# Instrumentation_Amp.net
KiCad netlist of a schematic drawn in Altium Designer
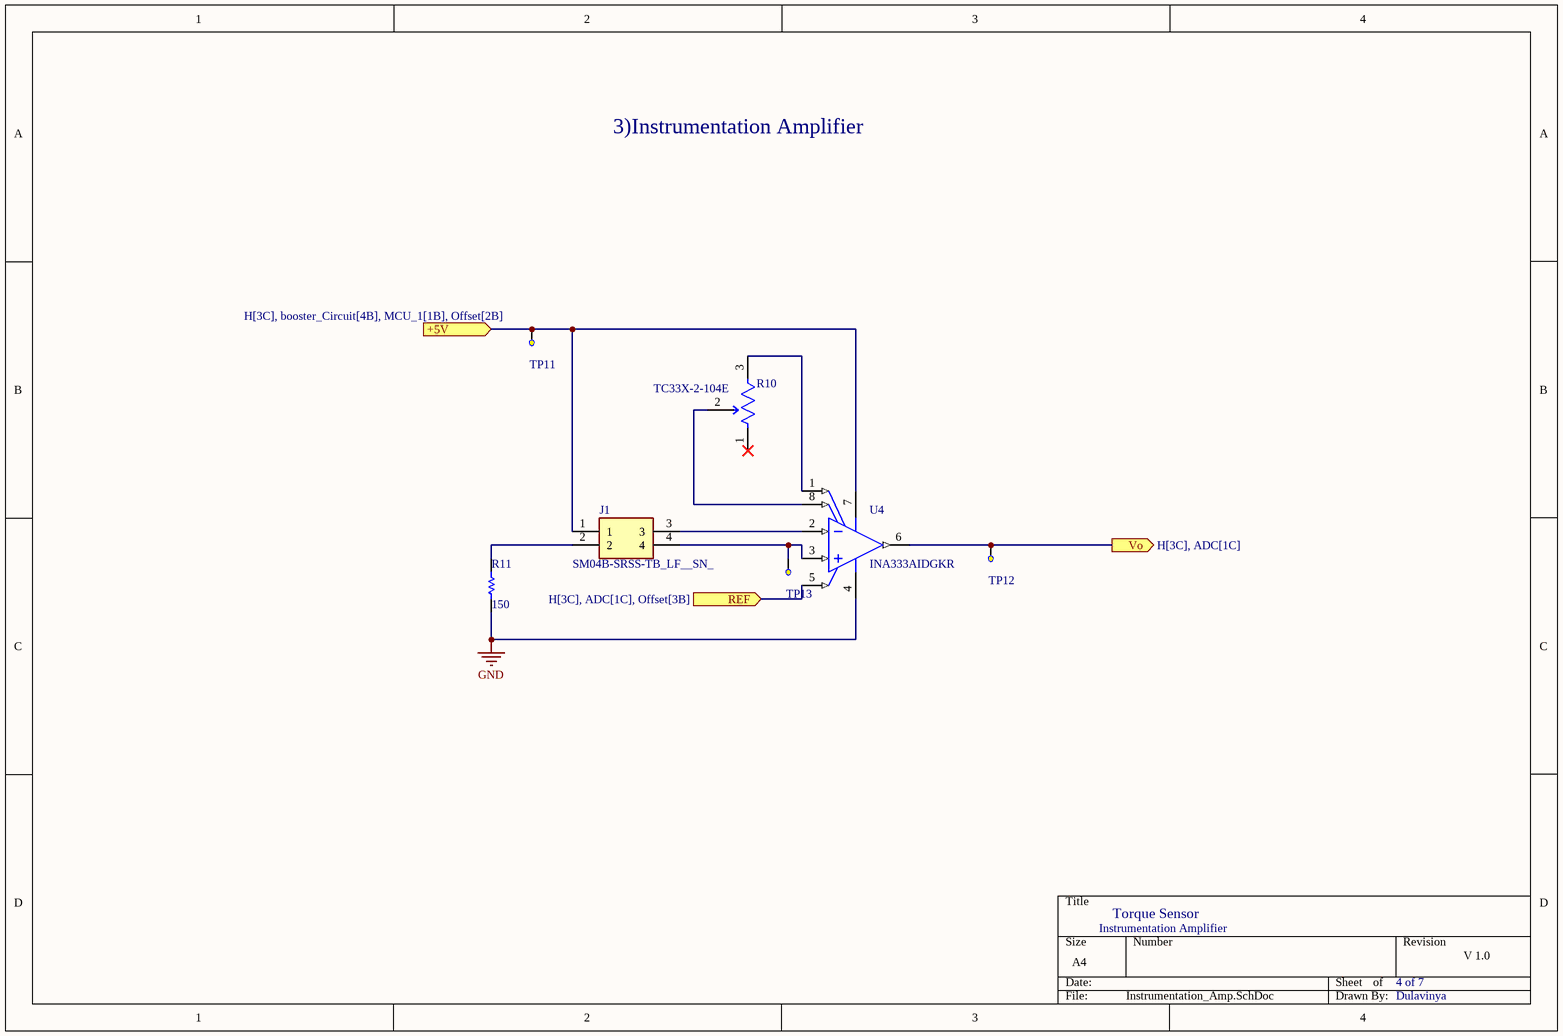
[diagram p0: Instrumentation_Amp.SchDoc]

(export (version "E")
  (design (tool "Eeschema 10.0.6"))
  (components
    (comp (ref "J1")
      (value "SM04B-SRSS-TB_LF__SN_")
      (footprint "SamacSys:SM04B-SRSS-TB(LFSN)")
      (description "Connector")
      (fields
        (field (name "MANUFACTURER_PART_NUMBER") "SM04B-SRSS-TB(LF)(SN)")
        (field (name "MOUSER PART NUMBER") "306-SM04BSRSSTBLFSN")
      )
      (libsource (lib "*") (part "SM04B-SRSS-TB_LF__SN_"))
    )
    (comp (ref "R10")
      (value "TC33X-2-104E")
      (footprint "FP-TC33X-2-MFG")
      (description "TRIMMER 100K OHM 0.1W J LEAD TOP")
      (fields (field (name "TOLERANCE") "25%"))
      (libsource (lib "Altium Content Vault") (part "13357d81287629c2fd191d242cfa50c"))
    )
    (comp (ref "R11")
      (value "150")
      (footprint "RESC1005X40X25LL05T10")
      (fields (field (name "PART NUMBER") "RC0402FR-07150RL") (field (name "MANUFACTURER") "Yageo / Phycomp"))
      (libsource (lib "Altium Content Vault") (part "RES"))
    )
    (comp (ref "TP11")
      (value "Test point")
      (footprint "Test_point")
      (libsource (lib "Schlib1") (part "test_point"))
    )
    (comp (ref "TP12")
      (value "Test point")
      (footprint "Test_point")
      (libsource (lib "Schlib1") (part "test_point"))
    )
    (comp (ref "TP13")
      (value "Test point")
      (footprint "Test_point")
      (libsource (lib "Schlib1") (part "test_point"))
    )
    (comp (ref "U4")
      (value "INA333AIDGKR")
      (footprint "DGK0008A_N")
      (fields (field (name "MANUFACTURER") "Texas Instruments"))
      (libsource (lib "Altium Content Vault") (part "TI-INAXXXXXX8"))
    )
  )
  (nets
    (net (code "1") (name "/+5V") (class "Default")
      (node (ref "J1") (pin "1") (pinfunction "1_1") (pintype "passive"))
      (node (ref "TP11") (pin "TP?") (pinfunction "Test_point_TP?") (pintype "passive"))
      (node (ref "U4") (pin "7") (pinfunction "V+_7") (pintype "power_in"))
    )
    (net (code "2") (name "/REF") (class "Default")
      (node (ref "U4") (pin "5") (pinfunction "REF_5") (pintype "input"))
    )
    (net (code "3") (name "/Vo") (class "Default")
      (node (ref "TP12") (pin "TP?") (pinfunction "Test_point_TP?") (pintype "passive"))
      (node (ref "U4") (pin "6") (pinfunction "VOUT_6") (pintype "output"))
    )
    (net (code "4") (name "GND") (class "Default")
      (node (ref "R11") (pin "1") (pinfunction "1_1") (pintype "passive"))
      (node (ref "U4") (pin "4") (pinfunction "V-_4") (pintype "power_in"))
    )
    (net (code "5") (name "Net-(J1-Pad2)") (class "Default")
      (node (ref "J1") (pin "2") (pinfunction "2_2") (pintype "passive"))
      (node (ref "R11") (pin "2") (pinfunction "2_2") (pintype "passive"))
    )
    (net (code "6") (name "Net-(R10-CW)") (class "Default")
      (node (ref "R10") (pin "3") (pinfunction "CW_3") (pintype "passive"))
      (node (ref "U4") (pin "1") (pinfunction "RG_1") (pintype "input"))
    )
    (net (code "7") (name "Net-(R10-WIPER)") (class "Default")
      (node (ref "R10") (pin "2") (pinfunction "WIPER_2") (pintype "passive"))
      (node (ref "U4") (pin "8") (pinfunction "RG_8") (pintype "input"))
    )
    (net (code "8") (name "Net-(TP13-Test_point)") (class "Default")
      (node (ref "J1") (pin "4") (pinfunction "4_4") (pintype "passive"))
      (node (ref "TP13") (pin "TP?") (pinfunction "Test_point_TP?") (pintype "passive"))
      (node (ref "U4") (pin "3") (pinfunction "VIN+_3") (pintype "input"))
    )
    (net (code "9") (name "Net-(U4-VIN-)") (class "Default")
      (node (ref "J1") (pin "3") (pinfunction "3_3") (pintype "passive"))
      (node (ref "U4") (pin "2") (pinfunction "VIN-_2") (pintype "input"))
    )
    (net (code "10") (name "unconnected-(R10-CCW-Pad1)") (class "Default")
      (node (ref "R10") (pin "1") (pinfunction "CCW_1") (pintype "passive+no_connect"))
    )
  )
)
